# SCHE_BUZZ.net
KiCad netlist of a schematic drawn in Altium Designer
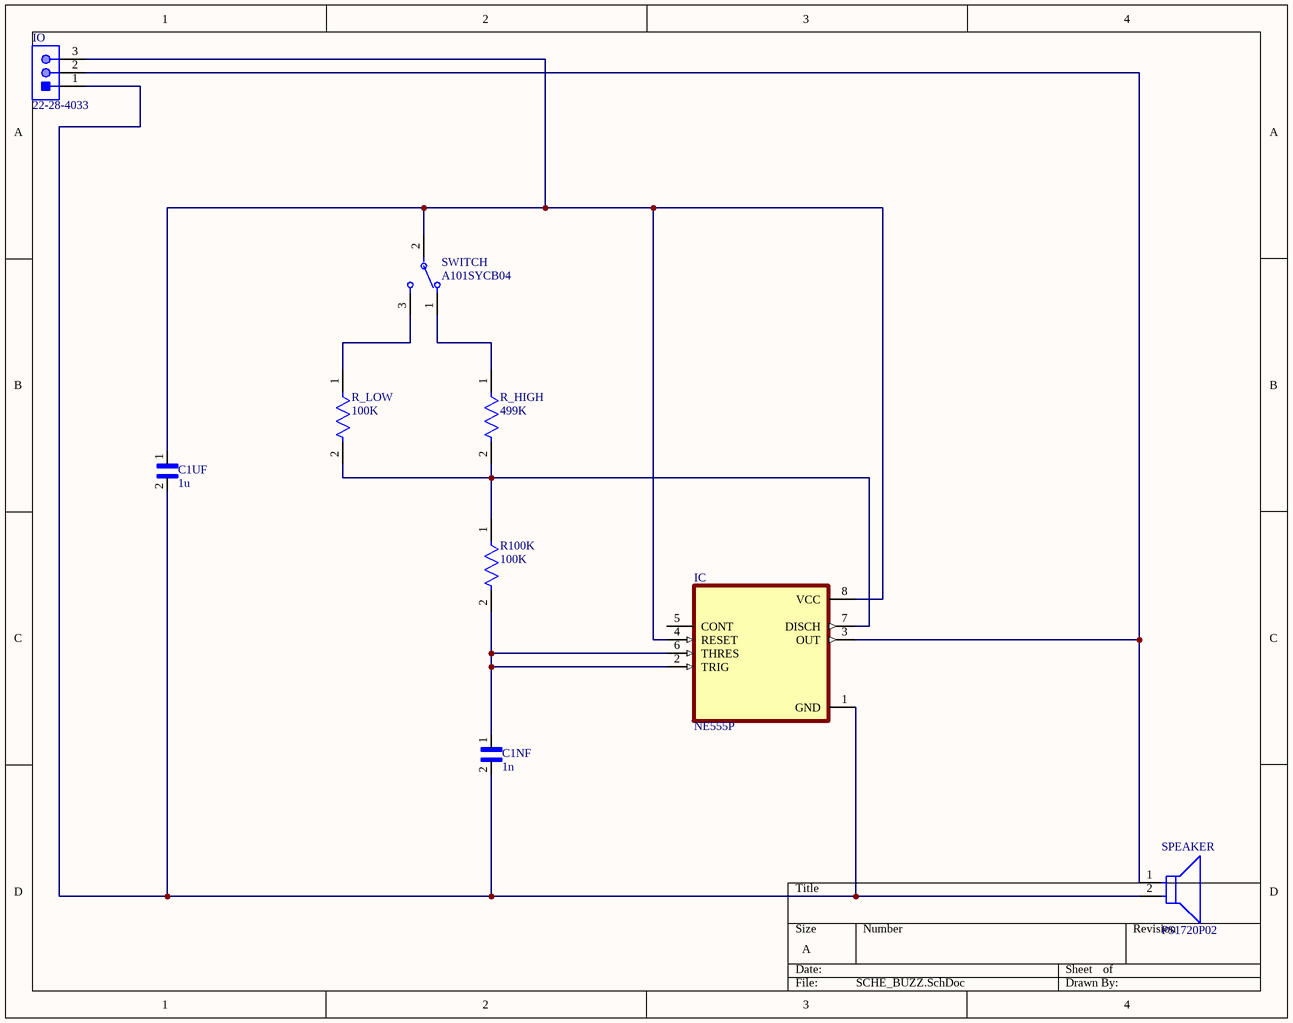
[diagram p0: SCHE_BUZZ.SchDoc]

(export (version "E")
  (design (tool "Eeschema 10.0.6"))
  (components
    (comp (ref "C1NF")
      (value "1n")
      (footprint "CAPRB500W50L750T400H800")
      (fields
        (field (name "MF") "TDK")
        (field (name "MP") "FK22X7R2A105KN000")
        (field (name "DIGI-KEY_PART_NUMBER") "445-FK22X7R2A105KN000-ND")
      )
      (libsource (lib "FK22X7R2A105KN000") (part "FK22X7R2A105KN000"))
    )
    (comp (ref "C1UF")
      (value "1u")
      (footprint "CAPRB500W50L750T400H800")
      (description "Cap Ceramic 1uF 100V X7R 10% Radial 5mm 125Â°C Tape and Box")
      (fields (field (name "MF") "TDK") (field (name "MP") "FK22X7R2A105KN000"))
      (libsource (lib "FK22X7R2A105KN000") (part "FK22X7R2A105KN000"))
    )
    (comp (ref "IC")
      (value "NE555P")
      (footprint "DIP794W45P254L959H508Q8")
      (libsource (lib "NE555P") (part "NE555P"))
    )
    (comp (ref "IO")
      (value "22-28-4033")
      (footprint "MOLX-22-28-4033_V")
      (description "Male Header, Pitch 2.54 mm, 1 x 3 Position, Height 8.38 mm, Tail Length 3.18 mm, RoHS, Bulk")
      (fields (field (name "MANUFACTURER") "Molex"))
      (libsource (lib "Altium Content Vault") (part "CN-1P-M-R3"))
    )
    (comp (ref "R100K")
      (value "100K")
      (footprint "FP-AC05000003909JAC00-0")
      (fields
        (field (name "OCTOPART") "https://octopart.com/ac05000003909jac00-vishay-39746279")
        (field (name "MANUFACTURER") "Vishay")
        (field (name "TOLERANCE") "5%")
      )
      (libsource (lib "Altium Content Vault") (part "1029c3af85768c4190bb7ad29bc67b5"))
    )
    (comp (ref "R_HIGH")
      (value "499K")
      (footprint "FP-AC05000003909JAC00-0")
      (fields
        (field (name "OCTOPART") "https://octopart.com/ac05000003909jac00-vishay-39746279")
        (field (name "MANUFACTURER") "Vishay")
        (field (name "TOLERANCE") "5%")
      )
      (libsource (lib "Altium Content Vault") (part "1029c3af85768c4190bb7ad29bc67b5"))
    )
    (comp (ref "R_LOW")
      (value "100K")
      (footprint "FP-AC05000003909JAC00-0")
      (fields
        (field (name "OCTOPART") "https://octopart.com/ac05000003909jac00-vishay-39746279")
        (field (name "MANUFACTURER") "Vishay")
        (field (name "TOLERANCE") "5%")
      )
      (libsource (lib "Altium Content Vault") (part "1029c3af85768c4190bb7ad29bc67b5"))
    )
    (comp (ref "SPEAKER")
      (value "PS1720P02")
      (footprint "FP-PS1720P02-MFG")
      (description "AUDIO PIEZO TRANSDUCER 30V TH")
      (fields
        (field (name "OCTOPART") "https://octopart.com/ps1720p02-tdk-154429")
        (field (name "MANUFACTURER") "TDK Corporation")
      )
      (libsource (lib "Altium Content Vault") (part "5f581d31613f872430949aa526fd155"))
    )
    (comp (ref "SWITCH")
      (value "A101SYCB04")
      (footprint "FP-A101SYCB04-MFG")
      (description "SWITCH TOGGLE SPDT 0.4VA 20V")
      (libsource (lib "Altium Content Vault") (part "52c419afdc2a387c7d548259a9aeefb"))
    )
  )
  (nets
    (net (code "1") (name "Net-(IC-DISCH)") (class "Default")
      (node (ref "IC") (pin "7") (pinfunction "DISCH_7") (pintype "output"))
      (node (ref "R100K") (pin "1") (pinfunction "1_1") (pintype "passive"))
      (node (ref "R_HIGH") (pin "2") (pinfunction "2_2") (pintype "passive"))
      (node (ref "R_LOW") (pin "2") (pinfunction "2_2") (pintype "passive"))
    )
    (net (code "2") (name "Net-(IC-GND)") (class "Default")
      (node (ref "C1NF") (pin "2") (pinfunction "2_2") (pintype "passive"))
      (node (ref "C1UF") (pin "2") (pinfunction "2_2") (pintype "passive"))
      (node (ref "IC") (pin "1") (pinfunction "GND_1") (pintype "power_in"))
      (node (ref "IO") (pin "1") (pinfunction "1_1") (pintype "passive"))
      (node (ref "SPEAKER") (pin "2") (pinfunction "2_2") (pintype "passive"))
    )
    (net (code "3") (name "Net-(IC-OUT)") (class "Default")
      (node (ref "IC") (pin "3") (pinfunction "OUT_3") (pintype "output"))
      (node (ref "IO") (pin "2") (pinfunction "2_2") (pintype "passive"))
      (node (ref "SPEAKER") (pin "1") (pinfunction "1_1") (pintype "passive"))
    )
    (net (code "4") (name "Net-(IC-RESET)") (class "Default")
      (node (ref "C1UF") (pin "1") (pinfunction "1_1") (pintype "passive"))
      (node (ref "IC") (pin "4") (pinfunction "RESET_4") (pintype "input"))
      (node (ref "IC") (pin "8") (pinfunction "VCC_8") (pintype "power_in"))
      (node (ref "IO") (pin "3") (pinfunction "3_3") (pintype "passive"))
      (node (ref "SWITCH") (pin "2") (pinfunction "2_2") (pintype "passive"))
    )
    (net (code "5") (name "Net-(IC-THRES)") (class "Default")
      (node (ref "C1NF") (pin "1") (pinfunction "1_1") (pintype "passive"))
      (node (ref "IC") (pin "2") (pinfunction "TRIG_2") (pintype "input"))
      (node (ref "IC") (pin "6") (pinfunction "THRES_6") (pintype "input"))
      (node (ref "R100K") (pin "2") (pinfunction "2_2") (pintype "passive"))
    )
    (net (code "6") (name "Net-(R_HIGH-Pad1)") (class "Default")
      (node (ref "R_HIGH") (pin "1") (pinfunction "1_1") (pintype "passive"))
      (node (ref "SWITCH") (pin "1") (pinfunction "1_1") (pintype "passive"))
    )
    (net (code "7") (name "Net-(R_LOW-Pad1)") (class "Default")
      (node (ref "R_LOW") (pin "1") (pinfunction "1_1") (pintype "passive"))
      (node (ref "SWITCH") (pin "3") (pinfunction "3_3") (pintype "passive"))
    )
    (net (code "8") (name "unconnected-(IC-CONT-Pad5)") (class "Default")
      (node (ref "IC") (pin "5") (pinfunction "CONT_5") (pintype "passive"))
    )
  )
)
